# OksLab_CanToUsb_HW01.net
KiCad netlist of a schematic drawn in Altium Designer
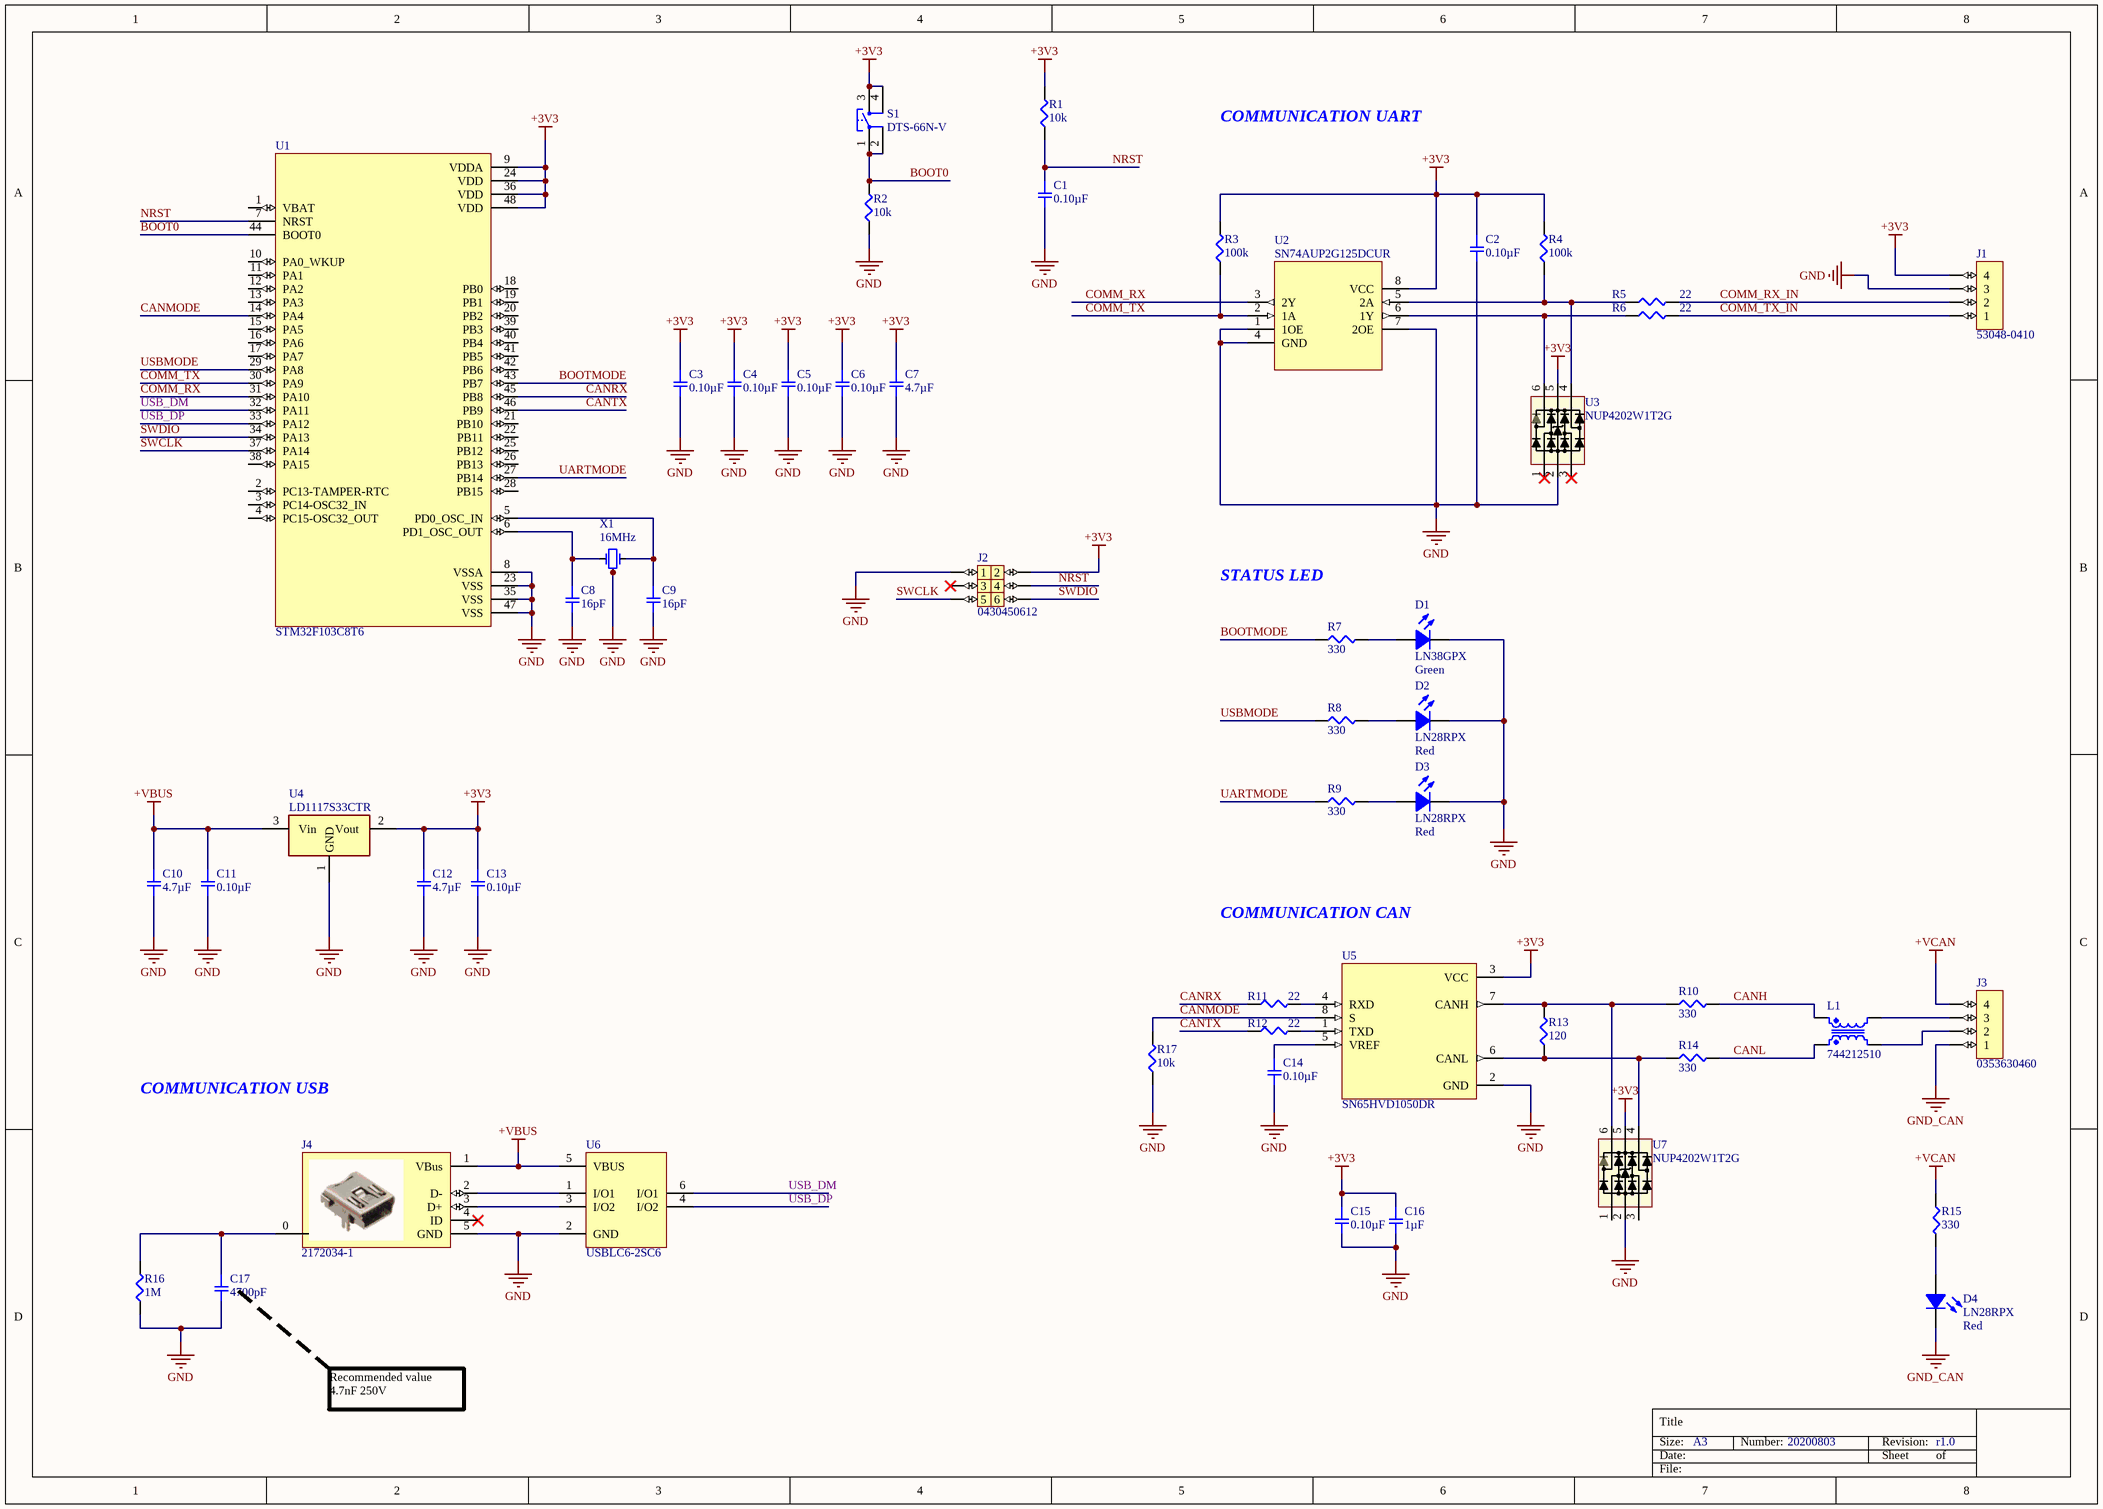
[diagram p0: OksLab_CanToUsb_HW01.SchDoc]

(export (version "E")
  (design (tool "Eeschema 10.0.6"))
  (components
    (comp (ref "C1")
      (value "0.10µF")
      (footprint "SMD-0603C")
      (description "CAP CER 0.1UF 50V X7R 0603")
      (fields
        (field (name "DIGI-KEY PART NUMBER") "490-5798-1-ND")
        (field (name "PART NUMBER") "GCJ188R71H104KA12D")
      )
      (libsource (lib "capacitor_murata_0603") (part "GCJ188R71H104KA12D"))
    )
    (comp (ref "C2")
      (value "0.10µF")
      (footprint "SMD-0603C")
      (description "CAP CER 0.1UF 50V X7R 0603")
      (fields
        (field (name "DIGI-KEY PART NUMBER") "490-5798-1-ND")
        (field (name "MANUFACTURER") "Murata Electronics North America")
      )
      (libsource (lib "capacitor_murata_0603") (part "GCJ188R71H104KA12D"))
    )
    (comp (ref "C3")
      (value "0.10µF")
      (footprint "SMD-0603C")
      (description "CAP CER 0.1UF 50V X7R 0603")
      (fields
        (field (name "DIGI-KEY PART NUMBER") "490-5798-1-ND")
        (field (name "PART NUMBER") "GCJ188R71H104KA12D")
      )
      (libsource (lib "capacitor_murata_0603") (part "GCJ188R71H104KA12D"))
    )
    (comp (ref "C4")
      (value "0.10µF")
      (footprint "SMD-0603C")
      (description "CAP CER 0.1UF 50V X7R 0603")
      (fields
        (field (name "DIGI-KEY PART NUMBER") "490-5798-1-ND")
        (field (name "PART NUMBER") "GCJ188R71H104KA12D")
      )
      (libsource (lib "capacitor_murata_0603") (part "GCJ188R71H104KA12D"))
    )
    (comp (ref "C5")
      (value "0.10µF")
      (footprint "SMD-0603C")
      (description "CAP CER 0.1UF 50V X7R 0603")
      (fields
        (field (name "DIGI-KEY PART NUMBER") "490-5798-1-ND")
        (field (name "PART NUMBER") "GCJ188R71H104KA12D")
      )
      (libsource (lib "capacitor_murata_0603") (part "GCJ188R71H104KA12D"))
    )
    (comp (ref "C6")
      (value "0.10µF")
      (footprint "SMD-0603C")
      (description "CAP CER 0.1UF 50V X7R 0603")
      (fields
        (field (name "DIGI-KEY PART NUMBER") "490-5798-1-ND")
        (field (name "PART NUMBER") "GCJ188R71H104KA12D")
      )
      (libsource (lib "capacitor_murata_0603") (part "GCJ188R71H104KA12D"))
    )
    (comp (ref "C7")
      (value "4.7µF")
      (footprint "SMD-0603C")
      (description "CAP CER 4.7UF 16V X5R 0603")
      (fields
        (field (name "DIGI-KEY PART NUMBER") "490-10481-1-ND")
        (field (name "PART NUMBER") "GRM188R61C475KAAJD")
      )
      (libsource (lib "capacitor_murata_0603") (part "GRM188R61C475KAAJD"))
    )
    (comp (ref "C8")
      (value "16pF")
      (footprint "SMD-0603C")
      (description "CAP CER 16PF 50V NP0 0603")
      (fields
        (field (name "DIGI-KEY PART NUMBER") "490-8003-1-ND")
        (field (name "PART NUMBER") "GCM1885C1H160JA16D")
      )
      (libsource (lib "capacitor_murata_0603") (part "GCM1885C1H160JA16D"))
    )
    (comp (ref "C9")
      (value "16pF")
      (footprint "SMD-0603C")
      (description "CAP CER 16PF 50V NP0 0603")
      (fields
        (field (name "DIGI-KEY PART NUMBER") "490-8003-1-ND")
        (field (name "PART NUMBER") "GCM1885C1H160JA16D")
      )
      (libsource (lib "capacitor_murata_0603") (part "GCM1885C1H160JA16D"))
    )
    (comp (ref "C10")
      (value "4.7µF")
      (footprint "SMD-0603C")
      (description "CAP CER 4.7UF 16V X5R 0603")
      (fields
        (field (name "DIGI-KEY PART NUMBER") "490-10481-1-ND")
        (field (name "PART NUMBER") "GRM188R61C475KAAJD")
      )
      (libsource (lib "capacitor_murata_0603") (part "GRM188R61C475KAAJD"))
    )
    (comp (ref "C11")
      (value "0.10µF")
      (footprint "SMD-0603C")
      (description "CAP CER 0.1UF 50V X7R 0603")
      (fields
        (field (name "DIGI-KEY PART NUMBER") "490-5798-1-ND")
        (field (name "PART NUMBER") "GCJ188R71H104KA12D")
      )
      (libsource (lib "capacitor_murata_0603") (part "GCJ188R71H104KA12D"))
    )
    (comp (ref "C12")
      (value "4.7µF")
      (footprint "SMD-0603C")
      (description "CAP CER 4.7UF 16V X5R 0603")
      (fields
        (field (name "DIGI-KEY PART NUMBER") "490-10481-1-ND")
        (field (name "PART NUMBER") "GRM188R61C475KAAJD")
      )
      (libsource (lib "capacitor_murata_0603") (part "GRM188R61C475KAAJD"))
    )
    (comp (ref "C13")
      (value "0.10µF")
      (footprint "SMD-0603C")
      (description "CAP CER 0.1UF 50V X7R 0603")
      (fields
        (field (name "DIGI-KEY PART NUMBER") "490-5798-1-ND")
        (field (name "PART NUMBER") "GCJ188R71H104KA12D")
      )
      (libsource (lib "capacitor_murata_0603") (part "GCJ188R71H104KA12D"))
    )
    (comp (ref "C14")
      (value "0.10µF")
      (footprint "SMD-0603C")
      (description "CAP CER 0.1UF 50V X7R 0603")
      (fields
        (field (name "DIGI-KEY PART NUMBER") "490-5798-1-ND")
        (field (name "PART NUMBER") "GCJ188R71H104KA12D")
      )
      (libsource (lib "capacitor_murata_0603") (part "GCJ188R71H104KA12D"))
    )
    (comp (ref "C15")
      (value "0.10µF")
      (footprint "SMD-0603C")
      (description "CAP CER 0.1UF 50V X7R 0603")
      (fields
        (field (name "DIGI-KEY PART NUMBER") "490-5798-1-ND")
        (field (name "PART NUMBER") "GCJ188R71H104KA12D")
      )
      (libsource (lib "capacitor_murata_0603") (part "GCJ188R71H104KA12D"))
    )
    (comp (ref "C16")
      (value "1µF")
      (footprint "SMD-0603C")
      (description "CAP CER 1UF 16V X7R 0603")
      (fields
        (field (name "DIGI-KEY PART NUMBER") "490-5241-1-ND")
        (field (name "PART NUMBER") "GCM188R71C105KA64D")
      )
      (libsource (lib "capacitor_murata_0603") (part "GCM188R71C105KA64D"))
    )
    (comp (ref "C17")
      (value "4700pF")
      (footprint "SMD-0805C")
      (description "CAP CER 4700PF 250V X7R 0805")
      (fields
        (field (name "DIGI-KEY PART NUMBER") "490-3532-1-ND")
        (field (name "MANUFACTURER") "Murata Electronics North America")
      )
      (libsource (lib "capacitor_murata_0805") (part "GRM21AR72E472KW01D"))
    )
    (comp (ref "D1")
      (value "LN38GPX")
      (footprint "Led-3mm-Green-h7")
      (description "LED GREEN 3MM ROUND T/H")
      (fields
        (field (name "MANUFACTURER") "Panasonic Electronic Components")
        (field (name "BASE PART NUMBER") "LN*8")
        (field (name "COLOR") "Green")
      )
      (libsource (lib "Altium_Lib") (part "LED_GREEN__LN38GPX"))
    )
    (comp (ref "D2")
      (value "LN28RPX")
      (footprint "Led-3mm-Red-h7")
      (description "LED RED DIFF 3MM ROUND T/H")
      (fields
        (field (name "MANUFACTURER") "Panasonic Electronic Components")
        (field (name "LENS COLOR") "Red")
      )
      (libsource (lib "Altium_Lib") (part "LED_RED__LN28RPX"))
    )
    (comp (ref "D3")
      (value "LN28RPX")
      (footprint "Led-3mm-Red-h7")
      (description "LED RED DIFF 3MM ROUND T/H")
      (fields
        (field (name "MANUFACTURER") "Panasonic Electronic Components")
        (field (name "LENS COLOR") "Red")
      )
      (libsource (lib "Altium_Lib") (part "LED_RED__LN28RPX"))
    )
    (comp (ref "D4")
      (value "LN28RPX")
      (footprint "Led-3mm-Red-h7")
      (description "LED RED DIFF 3MM ROUND T/H")
      (fields
        (field (name "MANUFACTURER") "Panasonic Electronic Components")
        (field (name "LENS COLOR") "Red")
      )
      (libsource (lib "Altium_Lib") (part "LED_RED__LN28RPX"))
    )
    (comp (ref "J1")
      (value "53048-0410")
      (footprint "CONN_4_POS__0530480410")
      (description "CONN HEADER R/A 4POS 1.25MM")
      (fields (field (name "MANUFACTURER") "Molex"))
      (libsource (lib "Altium_Lib") (part "CONN_4_POS__0530480410"))
    )
    (comp (ref "J2")
      (value "0430450612")
      (footprint "CONN_6_POS__0430450612")
      (description "CONN HEADER 6POS 3MM VERT TIN")
      (fields (field (name "MANUFACTURER") "Molex, LLC"))
      (libsource (lib "Altium_Lib") (part "CONN_6_POS__0430450612"))
    )
    (comp (ref "J3")
      (value "0353630460")
      (footprint "CONN_4_POS__0353630460")
      (description "CONN HEADER 4POS 2MM R/A TIN")
      (fields (field (name "MANUFACTURER") "Molex Connector Corporation"))
      (libsource (lib "Altium_Lib") (part "CONN_4_POS__0353630460"))
    )
    (comp (ref "J4")
      (value "2172034-1")
      (footprint "USB_MINI__2172034-1")
      (description "CONN RCPT USB2.0 MINI B 5P R/A")
      (fields (field (name "MANUFACTURER") "TE Connectivity AMP"))
      (libsource (lib "Altium_Lib") (part "USB_MINI__2172034-1"))
    )
    (comp (ref "L1")
      (value "744212510")
      (footprint "CM_6.50mm x 3.60mm")
      (description "Common Mode Filters / Chokes WE-SL1 SMD Ln Filter 2x51uH 300ohm")
      (fields (field (name "MANUFACTURER") "Wurth Electronics") (field (name "TOLERANCE") "50%"))
      (libsource (lib "Altium_Lib") (part "CM__744212510"))
    )
    (comp (ref "R1")
      (value "10k")
      (footprint "SMD-0603-RES")
      (description "RES SMD 10K OHM 1% 1/10W 0603")
      (fields
        (field (name "PART NUMBER") "ERJ-3EKF1002V")
        (field (name "DIGI-KEY PART NUMBER") "P10.0KHCT-ND")
      )
      (libsource (lib "Panasonic_ERJ_0603") (part "ERJ-3EKF1002V"))
    )
    (comp (ref "R2")
      (value "10k")
      (footprint "SMD-0603-RES")
      (description "RES SMD 10K OHM 1% 1/10W 0603")
      (fields
        (field (name "PART NUMBER") "ERJ-3EKF1002V")
        (field (name "DIGI-KEY PART NUMBER") "P10.0KHCT-ND")
      )
      (libsource (lib "Panasonic_ERJ_0603") (part "ERJ-3EKF1002V"))
    )
    (comp (ref "R3")
      (value "100k")
      (footprint "SMD-0603-RES")
      (description "RES SMD 100K OHM 1% 1/10W 0603")
      (fields
        (field (name "PART NUMBER") "ERJ-3EKF1003V")
        (field (name "DIGI-KEY PART NUMBER") "P100KHCT-ND")
      )
      (libsource (lib "Panasonic_ERJ_0603") (part "ERJ-3EKF1003V"))
    )
    (comp (ref "R4")
      (value "100k")
      (footprint "SMD-0603-RES")
      (description "RES SMD 100K OHM 1% 1/10W 0603")
      (fields
        (field (name "PART NUMBER") "ERJ-3EKF1003V")
        (field (name "DIGI-KEY PART NUMBER") "P100KHCT-ND")
      )
      (libsource (lib "Panasonic_ERJ_0603") (part "ERJ-3EKF1003V"))
    )
    (comp (ref "R5")
      (value "22")
      (footprint "SMD-0603-RES")
      (description "RES SMD 22 OHM 1% 1/10W 0603")
      (fields
        (field (name "PART NUMBER") "ERJ-3EKF22R0V")
        (field (name "DIGI-KEY PART NUMBER") "P22.0HCT-ND")
      )
      (libsource (lib "Panasonic_ERJ_0603") (part "ERJ-3EKF22R0V"))
    )
    (comp (ref "R6")
      (value "22")
      (footprint "SMD-0603-RES")
      (description "RES SMD 22 OHM 1% 1/10W 0603")
      (fields
        (field (name "PART NUMBER") "ERJ-3EKF22R0V")
        (field (name "DIGI-KEY PART NUMBER") "P22.0HCT-ND")
      )
      (libsource (lib "Panasonic_ERJ_0603") (part "ERJ-3EKF22R0V"))
    )
    (comp (ref "R7")
      (value "330")
      (footprint "SMD-0603-RES")
      (description "RES SMD 330 OHM 1% 1/10W 0603")
      (fields (field (name "PART NUMBER") "ERJ-3EKF3300V") (field (name "DIGI-KEY PART NUMBER") "P330HCT-ND"))
      (libsource (lib "Panasonic_ERJ_0603") (part "ERJ-3EKF3300V"))
    )
    (comp (ref "R8")
      (value "330")
      (footprint "SMD-0603-RES")
      (description "RES SMD 330 OHM 1% 1/10W 0603")
      (fields (field (name "PART NUMBER") "ERJ-3EKF3300V") (field (name "DIGI-KEY PART NUMBER") "P330HCT-ND"))
      (libsource (lib "Panasonic_ERJ_0603") (part "ERJ-3EKF3300V"))
    )
    (comp (ref "R9")
      (value "330")
      (footprint "SMD-0603-RES")
      (description "RES SMD 330 OHM 1% 1/10W 0603")
      (fields (field (name "PART NUMBER") "ERJ-3EKF3300V") (field (name "DIGI-KEY PART NUMBER") "P330HCT-ND"))
      (libsource (lib "Panasonic_ERJ_0603") (part "ERJ-3EKF3300V"))
    )
    (comp (ref "R10")
      (value "330")
      (footprint "SMD-0603-RES")
      (description "RES SMD 330 OHM 1% 1/10W 0603")
      (fields (field (name "PART NUMBER") "ERJ-3EKF3300V") (field (name "DIGI-KEY PART NUMBER") "P330HCT-ND"))
      (libsource (lib "Panasonic_ERJ_0603") (part "ERJ-3EKF3300V"))
    )
    (comp (ref "R11")
      (value "22")
      (footprint "SMD-0603-RES")
      (description "RES SMD 22 OHM 1% 1/10W 0603")
      (fields
        (field (name "PART NUMBER") "ERJ-3EKF22R0V")
        (field (name "DIGI-KEY PART NUMBER") "P22.0HCT-ND")
      )
      (libsource (lib "Panasonic_ERJ_0603") (part "ERJ-3EKF22R0V"))
    )
    (comp (ref "R12")
      (value "22")
      (footprint "SMD-0603-RES")
      (description "RES SMD 22 OHM 1% 1/10W 0603")
      (fields
        (field (name "PART NUMBER") "ERJ-3EKF22R0V")
        (field (name "DIGI-KEY PART NUMBER") "P22.0HCT-ND")
      )
      (libsource (lib "Panasonic_ERJ_0603") (part "ERJ-3EKF22R0V"))
    )
    (comp (ref "R13")
      (value "120")
      (footprint "SMD-0603-RES")
      (description "RES SMD 120 OHM 1% 1/10W 0603")
      (fields (field (name "PART NUMBER") "ERJ-3EKF1200V") (field (name "DIGI-KEY PART NUMBER") "P120HCT-ND"))
      (libsource (lib "Panasonic_ERJ_0603") (part "ERJ-3EKF1200V"))
    )
    (comp (ref "R14")
      (value "330")
      (footprint "SMD-0603-RES")
      (description "RES SMD 330 OHM 1% 1/10W 0603")
      (fields (field (name "PART NUMBER") "ERJ-3EKF3300V") (field (name "DIGI-KEY PART NUMBER") "P330HCT-ND"))
      (libsource (lib "Panasonic_ERJ_0603") (part "ERJ-3EKF3300V"))
    )
    (comp (ref "R15")
      (value "330")
      (footprint "SMD-0603-RES")
      (description "RES SMD 330 OHM 1% 1/10W 0603")
      (fields (field (name "PART NUMBER") "ERJ-3EKF3300V") (field (name "DIGI-KEY PART NUMBER") "P330HCT-ND"))
      (libsource (lib "Panasonic_ERJ_0603") (part "ERJ-3EKF3300V"))
    )
    (comp (ref "R16")
      (value "1M")
      (footprint "SMD-0603-RES")
      (description "RES SMD 1M OHM 1% 1/10W 0603")
      (fields
        (field (name "DIGI-KEY PART NUMBER") "P1.00MHCT-ND")
        (field (name "MANUFACTURER") "Panasonic Electronic Components")
      )
      (libsource (lib "Panasonic_ERJ_0603") (part "ERJ-3EKF1004V"))
    )
    (comp (ref "R17")
      (value "10k")
      (footprint "SMD-0603-RES")
      (description "RES SMD 10K OHM 1% 1/10W 0603")
      (fields
        (field (name "PART NUMBER") "ERJ-3EKF1002V")
        (field (name "DIGI-KEY PART NUMBER") "P10.0KHCT-ND")
      )
      (libsource (lib "Panasonic_ERJ_0603") (part "ERJ-3EKF1002V"))
    )
    (comp (ref "S1")
      (value "DTS-66N-V")
      (footprint "Tact_THD_6x6_13mm")
      (description "Tactile Switches 6x6mm 13mm 160gf BROWN")
      (fields (field (name "MANUFACTURER") "Diptronics"))
      (libsource (lib "Altium_Lib") (part "SWITCH_TACTILE__DTS-66N-V"))
    )
    (comp (ref "U1")
      (value "STM32F103C8T6")
      (footprint "QFN48-(7mmX7mm)")
      (description "IC MCU 32-Bit 72MHz 64kB FLASH LQFP48")
      (fields (field (name "MF") "STMicroelectronics"))
      (libsource (lib "Altium_Lib") (part "STM32F103C8T6"))
    )
    (comp (ref "U2")
      (value "SN74AUP2G125DCUR")
      (footprint "VFSOP_8")
      (description "Low-Power Dual Bus Buffer Gate With 3-State Outputs 8-VSSOP -40 to 85")
      (fields (field (name "MANUFACTURER") "Texas Instruments"))
      (libsource (lib "Altium_Lib") (part "SN74AUP2G125DCUR"))
    )
    (comp (ref "U3")
      (value "NUP4202W1T2G")
      (footprint "SOT-363")
      (description "TVS DIODE 5VWM 14.5VC SOT363")
      (fields (field (name "MANUFACTURER") "ON Semiconductor"))
      (libsource (lib "Altium_Lib") (part "NUP4202W1T2G"))
    )
    (comp (ref "U4")
      (value "LD1117S33CTR")
      (footprint "SOT223-3N")
      (description "STMICROELECTRONICS - LD1117S33CTR - IC, V REG, LDO 3.3V, SMD")
      (fields (field (name "MANUFACTURER") "STMICROELECTRONICS"))
      (libsource (lib "Altium_Lib") (part "LD1117S33TR"))
    )
    (comp (ref "U5")
      (value "SN65HVD1050DR")
      (footprint "SOIC-8_L")
      (description "High-Speed CAN Transceiver with Silent Mode 8-SOIC -40 to 125")
      (fields (field (name "DIGI-KEY_PART_NUMBER") "296-26335-1-ND") (field (name "MF") "Texas Instruments"))
      (libsource (lib "Altium_Lib") (part "SN65HVD1050DR"))
    )
    (comp (ref "U6")
      (value "USBLC6-2SC6")
      (footprint "SOT23-6")
      (description "TVS DIODE 5.25V 17V SOT23-6")
      (fields (field (name "MANUFACTURER") "STMicroelectronics") (field (name "BASE PART NUMBER") "USBLC6-2"))
      (libsource (lib "KRNK_Altium") (part "USBLC6-2SC6"))
    )
    (comp (ref "U7")
      (value "NUP4202W1T2G")
      (footprint "SOT-363")
      (description "TVS DIODE 5VWM 14.5VC SOT363")
      (fields (field (name "MANUFACTURER") "ON Semiconductor"))
      (libsource (lib "Altium_Lib") (part "NUP4202W1T2G"))
    )
    (comp (ref "X1")
      (value "7M-16.000MAAJ-T")
      (footprint "XTAL_3.2mm_2.5mm_4pad")
      (description "Crystal 16MHz ±30ppm (Tol) ±30ppm (Stability) 18pF FUND 100Ohm 4-Pin SMD T/R")
      (fields
        (field (name "MANUFACTURER") "TXC")
        (field (name "FREQUENCY") "16MHz")
        (field (name "TOLERANCE") "30ppm")
      )
      (libsource (lib "Altium_Lib") (part "CRYSTAL__7M-16.000MAAJ-T"))
    )
  )
  (nets
    (net (code "1") (name "+3V3") (class "Default")
      (node (ref "C12") (pin "1") (pinfunction "1_1") (pintype "passive"))
      (node (ref "C13") (pin "1") (pinfunction "1_1") (pintype "passive"))
      (node (ref "C15") (pin "1") (pinfunction "1_1") (pintype "passive"))
      (node (ref "C16") (pin "1") (pinfunction "1_1") (pintype "passive"))
      (node (ref "C2") (pin "1") (pinfunction "1_1") (pintype "passive"))
      (node (ref "C3") (pin "1") (pinfunction "1_1") (pintype "passive"))
      (node (ref "C4") (pin "1") (pinfunction "1_1") (pintype "passive"))
      (node (ref "C5") (pin "1") (pinfunction "1_1") (pintype "passive"))
      (node (ref "C6") (pin "1") (pinfunction "1_1") (pintype "passive"))
      (node (ref "C7") (pin "1") (pinfunction "1_1") (pintype "passive"))
      (node (ref "J1") (pin "4") (pinfunction "4_4") (pintype "bidirectional"))
      (node (ref "J2") (pin "2") (pinfunction "2_2") (pintype "bidirectional"))
      (node (ref "R1") (pin "2") (pinfunction "2_2") (pintype "passive"))
      (node (ref "R3") (pin "2") (pinfunction "2_2") (pintype "passive"))
      (node (ref "R4") (pin "2") (pinfunction "2_2") (pintype "passive"))
      (node (ref "S1") (pin "3") (pinfunction "3_3") (pintype "passive"))
      (node (ref "S1") (pin "4") (pinfunction "4_4") (pintype "passive"))
      (node (ref "U1") (pin "24") (pinfunction "VDD_24") (pintype "passive"))
      (node (ref "U1") (pin "36") (pinfunction "VDD_36") (pintype "passive"))
      (node (ref "U1") (pin "48") (pinfunction "VDD_48") (pintype "passive"))
      (node (ref "U1") (pin "9") (pinfunction "VDDA_9") (pintype "passive"))
      (node (ref "U2") (pin "8") (pinfunction "VCC_8") (pintype "passive"))
      (node (ref "U3") (pin "5") (pinfunction "5_5") (pintype "passive"))
      (node (ref "U4") (pin "2") (pinfunction "Vout_2") (pintype "passive"))
      (node (ref "U5") (pin "3") (pinfunction "VCC_3") (pintype "power_in"))
      (node (ref "U7") (pin "5") (pinfunction "5_5") (pintype "passive"))
    )
    (net (code "2") (name "+VBUS") (class "Default")
      (node (ref "C10") (pin "1") (pinfunction "1_1") (pintype "passive"))
      (node (ref "C11") (pin "1") (pinfunction "1_1") (pintype "passive"))
      (node (ref "J4") (pin "1") (pinfunction "VBus_1") (pintype "power_in"))
      (node (ref "U4") (pin "3") (pinfunction "Vin_3") (pintype "passive"))
      (node (ref "U6") (pin "5") (pinfunction "VBUS_5") (pintype "passive"))
    )
    (net (code "3") (name "+VCAN") (class "Default")
      (node (ref "J3") (pin "4") (pinfunction "4_4") (pintype "bidirectional"))
      (node (ref "R15") (pin "1") (pinfunction "1_1") (pintype "passive"))
    )
    (net (code "4") (name "/BOOT0") (class "Default")
      (node (ref "R2") (pin "2") (pinfunction "2_2") (pintype "passive"))
      (node (ref "S1") (pin "1") (pinfunction "1_1") (pintype "passive"))
      (node (ref "S1") (pin "2") (pinfunction "2_2") (pintype "passive"))
      (node (ref "U1") (pin "44") (pinfunction "BOOT0_44") (pintype "passive"))
    )
    (net (code "5") (name "/BOOTMODE") (class "Default")
      (node (ref "R7") (pin "1") (pinfunction "1_1") (pintype "passive"))
      (node (ref "U1") (pin "43") (pinfunction "PB7_43") (pintype "bidirectional"))
    )
    (net (code "6") (name "/CANH") (class "Default")
      (node (ref "L1") (pin "3") (pinfunction "3_3") (pintype "passive"))
      (node (ref "R10") (pin "2") (pinfunction "2_2") (pintype "passive"))
    )
    (net (code "7") (name "/CANL") (class "Default")
      (node (ref "L1") (pin "1") (pinfunction "1_1") (pintype "passive"))
      (node (ref "R14") (pin "2") (pinfunction "2_2") (pintype "passive"))
    )
    (net (code "8") (name "/CANMODE") (class "Default")
      (node (ref "R17") (pin "2") (pinfunction "2_2") (pintype "passive"))
      (node (ref "U1") (pin "14") (pinfunction "PA4_14") (pintype "bidirectional"))
      (node (ref "U5") (pin "8") (pinfunction "S_8") (pintype "input"))
    )
    (net (code "9") (name "/CANRX") (class "Default")
      (node (ref "R11") (pin "1") (pinfunction "1_1") (pintype "passive"))
      (node (ref "U1") (pin "45") (pinfunction "PB8_45") (pintype "bidirectional"))
    )
    (net (code "10") (name "/CANTX") (class "Default")
      (node (ref "R12") (pin "1") (pinfunction "1_1") (pintype "passive"))
      (node (ref "U1") (pin "46") (pinfunction "PB9_46") (pintype "bidirectional"))
    )
    (net (code "11") (name "/COMM_RX") (class "Default")
      (node (ref "U1") (pin "31") (pinfunction "PA10_31") (pintype "bidirectional"))
      (node (ref "U2") (pin "3") (pinfunction "2Y_3") (pintype "output"))
    )
    (net (code "12") (name "/COMM_RX_IN") (class "Default")
      (node (ref "J1") (pin "2") (pinfunction "2_2") (pintype "bidirectional"))
      (node (ref "R5") (pin "2") (pinfunction "2_2") (pintype "passive"))
    )
    (net (code "13") (name "/COMM_TX") (class "Default")
      (node (ref "R3") (pin "1") (pinfunction "1_1") (pintype "passive"))
      (node (ref "U1") (pin "30") (pinfunction "PA9_30") (pintype "bidirectional"))
      (node (ref "U2") (pin "2") (pinfunction "1A_2") (pintype "input"))
    )
    (net (code "14") (name "/COMM_TX_IN") (class "Default")
      (node (ref "J1") (pin "1") (pinfunction "1_1") (pintype "bidirectional"))
      (node (ref "R6") (pin "2") (pinfunction "2_2") (pintype "passive"))
    )
    (net (code "15") (name "/NRST") (class "Default")
      (node (ref "C1") (pin "1") (pinfunction "1_1") (pintype "passive"))
      (node (ref "J2") (pin "4") (pinfunction "4_4") (pintype "bidirectional"))
      (node (ref "R1") (pin "1") (pinfunction "1_1") (pintype "passive"))
      (node (ref "U1") (pin "7") (pinfunction "NRST_7") (pintype "passive"))
    )
    (net (code "16") (name "/SWCLK") (class "Default")
      (node (ref "J2") (pin "5") (pinfunction "5_5") (pintype "bidirectional"))
      (node (ref "U1") (pin "37") (pinfunction "PA14_37") (pintype "bidirectional"))
    )
    (net (code "17") (name "/SWDIO") (class "Default")
      (node (ref "J2") (pin "6") (pinfunction "6_6") (pintype "bidirectional"))
      (node (ref "U1") (pin "34") (pinfunction "PA13_34") (pintype "bidirectional"))
    )
    (net (code "18") (name "/UARTMODE") (class "Default")
      (node (ref "R9") (pin "1") (pinfunction "1_1") (pintype "passive"))
      (node (ref "U1") (pin "27") (pinfunction "PB14_27") (pintype "bidirectional"))
    )
    (net (code "19") (name "/USBMODE") (class "Default")
      (node (ref "R8") (pin "1") (pinfunction "1_1") (pintype "passive"))
      (node (ref "U1") (pin "29") (pinfunction "PA8_29") (pintype "bidirectional"))
    )
    (net (code "20") (name "/USB_DM") (class "Default")
      (node (ref "U1") (pin "32") (pinfunction "PA11_32") (pintype "bidirectional"))
      (node (ref "U6") (pin "6") (pinfunction "I/O1_6") (pintype "passive"))
    )
    (net (code "21") (name "/USB_DP") (class "Default")
      (node (ref "U1") (pin "33") (pinfunction "PA12_33") (pintype "bidirectional"))
      (node (ref "U6") (pin "4") (pinfunction "I/O2_4") (pintype "passive"))
    )
    (net (code "22") (name "GND") (class "Default")
      (node (ref "C1") (pin "2") (pinfunction "2_2") (pintype "passive"))
      (node (ref "C10") (pin "2") (pinfunction "2_2") (pintype "passive"))
      (node (ref "C11") (pin "2") (pinfunction "2_2") (pintype "passive"))
      (node (ref "C12") (pin "2") (pinfunction "2_2") (pintype "passive"))
      (node (ref "C13") (pin "2") (pinfunction "2_2") (pintype "passive"))
      (node (ref "C14") (pin "2") (pinfunction "2_2") (pintype "passive"))
      (node (ref "C15") (pin "2") (pinfunction "2_2") (pintype "passive"))
      (node (ref "C16") (pin "2") (pinfunction "2_2") (pintype "passive"))
      (node (ref "C17") (pin "2") (pinfunction "2_2") (pintype "passive"))
      (node (ref "C2") (pin "2") (pinfunction "2_2") (pintype "passive"))
      (node (ref "C3") (pin "2") (pinfunction "2_2") (pintype "passive"))
      (node (ref "C4") (pin "2") (pinfunction "2_2") (pintype "passive"))
      (node (ref "C5") (pin "2") (pinfunction "2_2") (pintype "passive"))
      (node (ref "C6") (pin "2") (pinfunction "2_2") (pintype "passive"))
      (node (ref "C7") (pin "2") (pinfunction "2_2") (pintype "passive"))
      (node (ref "C8") (pin "2") (pinfunction "2_2") (pintype "passive"))
      (node (ref "C9") (pin "2") (pinfunction "2_2") (pintype "passive"))
      (node (ref "D1") (pin "2") (pinfunction "K_2") (pintype "passive"))
      (node (ref "D2") (pin "2") (pinfunction "K_2") (pintype "passive"))
      (node (ref "D3") (pin "2") (pinfunction "K_2") (pintype "passive"))
      (node (ref "J1") (pin "3") (pinfunction "3_3") (pintype "bidirectional"))
      (node (ref "J2") (pin "1") (pinfunction "1_1") (pintype "bidirectional"))
      (node (ref "J4") (pin "5") (pinfunction "GND_5") (pintype "power_in"))
      (node (ref "R16") (pin "1") (pinfunction "1_1") (pintype "passive"))
      (node (ref "R17") (pin "1") (pinfunction "1_1") (pintype "passive"))
      (node (ref "R2") (pin "1") (pinfunction "1_1") (pintype "passive"))
      (node (ref "U1") (pin "23") (pinfunction "VSS_23") (pintype "passive"))
      (node (ref "U1") (pin "35") (pinfunction "VSS_35") (pintype "passive"))
      (node (ref "U1") (pin "47") (pinfunction "VSS_47") (pintype "passive"))
      (node (ref "U1") (pin "8") (pinfunction "VSSA_8") (pintype "passive"))
      (node (ref "U2") (pin "1") (pinfunction "1OE_1") (pintype "passive"))
      (node (ref "U2") (pin "4") (pinfunction "GND_4") (pintype "passive"))
      (node (ref "U2") (pin "7") (pinfunction "2OE_7") (pintype "passive"))
      (node (ref "U3") (pin "2") (pinfunction "2_2") (pintype "passive"))
      (node (ref "U4") (pin "1") (pinfunction "GND_1") (pintype "passive"))
      (node (ref "U5") (pin "2") (pinfunction "GND_2") (pintype "power_in"))
      (node (ref "U6") (pin "2") (pinfunction "GND_2") (pintype "passive"))
      (node (ref "U7") (pin "2") (pinfunction "2_2") (pintype "passive"))
      (node (ref "X1") (pin "2") (pinfunction "GND_2") (pintype "power_in"))
      (node (ref "X1") (pin "4") (pinfunction "GND_4") (pintype "power_in"))
    )
    (net (code "23") (name "GND_CAN") (class "Default")
      (node (ref "D4") (pin "2") (pinfunction "K_2") (pintype "passive"))
      (node (ref "J3") (pin "1") (pinfunction "1_1") (pintype "bidirectional"))
    )
    (net (code "24") (name "Net-(D1-A)") (class "Default")
      (node (ref "D1") (pin "1") (pinfunction "A_1") (pintype "passive"))
      (node (ref "R7") (pin "2") (pinfunction "2_2") (pintype "passive"))
    )
    (net (code "25") (name "Net-(D2-A)") (class "Default")
      (node (ref "D2") (pin "1") (pinfunction "A_1") (pintype "passive"))
      (node (ref "R8") (pin "2") (pinfunction "2_2") (pintype "passive"))
    )
    (net (code "26") (name "Net-(D3-A)") (class "Default")
      (node (ref "D3") (pin "1") (pinfunction "A_1") (pintype "passive"))
      (node (ref "R9") (pin "2") (pinfunction "2_2") (pintype "passive"))
    )
    (net (code "27") (name "Net-(D4-A)") (class "Default")
      (node (ref "D4") (pin "1") (pinfunction "A_1") (pintype "passive"))
      (node (ref "R15") (pin "2") (pinfunction "2_2") (pintype "passive"))
    )
    (net (code "28") (name "Net-(J3-Pad2)") (class "Default")
      (node (ref "J3") (pin "2") (pinfunction "2_2") (pintype "bidirectional"))
      (node (ref "L1") (pin "5") (pinfunction "5_5") (pintype "passive"))
    )
    (net (code "29") (name "Net-(J3-Pad3)") (class "Default")
      (node (ref "J3") (pin "3") (pinfunction "3_3") (pintype "bidirectional"))
      (node (ref "L1") (pin "4") (pinfunction "4_4") (pintype "passive"))
    )
    (net (code "30") (name "Net-(J4-D+)") (class "Default")
      (node (ref "J4") (pin "3") (pinfunction "D+_3") (pintype "bidirectional"))
      (node (ref "U6") (pin "3") (pinfunction "I/O2_3") (pintype "passive"))
    )
    (net (code "31") (name "Net-(J4-D-)") (class "Default")
      (node (ref "J4") (pin "2") (pinfunction "D-_2") (pintype "bidirectional"))
      (node (ref "U6") (pin "1") (pinfunction "I/O1_1") (pintype "passive"))
    )
    (net (code "32") (name "Net-(J4-Shield)") (class "Default")
      (node (ref "C17") (pin "1") (pinfunction "1_1") (pintype "passive"))
      (node (ref "J4") (pin "0") (pinfunction "Shield_0") (pintype "passive"))
      (node (ref "R16") (pin "2") (pinfunction "2_2") (pintype "passive"))
    )
    (net (code "33") (name "Net-(U1-PD0_OSC_IN)") (class "Default")
      (node (ref "C9") (pin "1") (pinfunction "1_1") (pintype "passive"))
      (node (ref "U1") (pin "5") (pinfunction "PD0_OSC_IN_5") (pintype "bidirectional"))
      (node (ref "X1") (pin "3") (pinfunction "OSC2_3") (pintype "passive"))
    )
    (net (code "34") (name "Net-(U1-PD1_OSC_OUT)") (class "Default")
      (node (ref "C8") (pin "1") (pinfunction "1_1") (pintype "passive"))
      (node (ref "U1") (pin "6") (pinfunction "PD1_OSC_OUT_6") (pintype "bidirectional"))
      (node (ref "X1") (pin "1") (pinfunction "OSC1_1") (pintype "passive"))
    )
    (net (code "35") (name "Net-(U2-1Y)") (class "Default")
      (node (ref "R6") (pin "1") (pinfunction "1_1") (pintype "passive"))
      (node (ref "U2") (pin "6") (pinfunction "1Y_6") (pintype "output"))
      (node (ref "U3") (pin "6") (pinfunction "6_6") (pintype "passive"))
    )
    (net (code "36") (name "Net-(U2-2A)") (class "Default")
      (node (ref "R4") (pin "1") (pinfunction "1_1") (pintype "passive"))
      (node (ref "R5") (pin "1") (pinfunction "1_1") (pintype "passive"))
      (node (ref "U2") (pin "5") (pinfunction "2A_5") (pintype "input"))
      (node (ref "U3") (pin "4") (pinfunction "4_4") (pintype "passive"))
    )
    (net (code "37") (name "Net-(U5-CANH)") (class "Default")
      (node (ref "R10") (pin "1") (pinfunction "1_1") (pintype "passive"))
      (node (ref "R13") (pin "2") (pinfunction "2_2") (pintype "passive"))
      (node (ref "U5") (pin "7") (pinfunction "CANH_7") (pintype "output"))
      (node (ref "U7") (pin "6") (pinfunction "6_6") (pintype "passive"))
    )
    (net (code "38") (name "Net-(U5-CANL)") (class "Default")
      (node (ref "R13") (pin "1") (pinfunction "1_1") (pintype "passive"))
      (node (ref "R14") (pin "1") (pinfunction "1_1") (pintype "passive"))
      (node (ref "U5") (pin "6") (pinfunction "CANL_6") (pintype "output"))
      (node (ref "U7") (pin "4") (pinfunction "4_4") (pintype "passive"))
    )
    (net (code "39") (name "Net-(U5-RXD)") (class "Default")
      (node (ref "R11") (pin "2") (pinfunction "2_2") (pintype "passive"))
      (node (ref "U5") (pin "4") (pinfunction "RXD_4") (pintype "input"))
    )
    (net (code "40") (name "Net-(U5-TXD)") (class "Default")
      (node (ref "R12") (pin "2") (pinfunction "2_2") (pintype "passive"))
      (node (ref "U5") (pin "1") (pinfunction "TXD_1") (pintype "input"))
    )
    (net (code "41") (name "Net-(U5-VREF)") (class "Default")
      (node (ref "C14") (pin "1") (pinfunction "1_1") (pintype "passive"))
      (node (ref "U5") (pin "5") (pinfunction "VREF_5") (pintype "input"))
    )
    (net (code "42") (name "unconnected-(J2-Pad3)") (class "Default")
      (node (ref "J2") (pin "3") (pinfunction "3_3") (pintype "bidirectional+no_connect"))
    )
    (net (code "43") (name "unconnected-(J4-ID-Pad4)") (class "Default")
      (node (ref "J4") (pin "4") (pinfunction "ID_4") (pintype "power_in+no_connect"))
    )
    (net (code "44") (name "unconnected-(U1-PA0_WKUP-Pad10)") (class "Default")
      (node (ref "U1") (pin "10") (pinfunction "PA0_WKUP_10") (pintype "bidirectional"))
    )
    (net (code "45") (name "unconnected-(U1-PA1-Pad11)") (class "Default")
      (node (ref "U1") (pin "11") (pinfunction "PA1_11") (pintype "bidirectional"))
    )
    (net (code "46") (name "unconnected-(U1-PA2-Pad12)") (class "Default")
      (node (ref "U1") (pin "12") (pinfunction "PA2_12") (pintype "bidirectional"))
    )
    (net (code "47") (name "unconnected-(U1-PA3-Pad13)") (class "Default")
      (node (ref "U1") (pin "13") (pinfunction "PA3_13") (pintype "bidirectional"))
    )
    (net (code "48") (name "unconnected-(U1-PA5-Pad15)") (class "Default")
      (node (ref "U1") (pin "15") (pinfunction "PA5_15") (pintype "bidirectional"))
    )
    (net (code "49") (name "unconnected-(U1-PA6-Pad16)") (class "Default")
      (node (ref "U1") (pin "16") (pinfunction "PA6_16") (pintype "bidirectional"))
    )
    (net (code "50") (name "unconnected-(U1-PA7-Pad17)") (class "Default")
      (node (ref "U1") (pin "17") (pinfunction "PA7_17") (pintype "bidirectional"))
    )
    (net (code "51") (name "unconnected-(U1-PA15-Pad38)") (class "Default")
      (node (ref "U1") (pin "38") (pinfunction "PA15_38") (pintype "bidirectional"))
    )
    (net (code "52") (name "unconnected-(U1-PB0-Pad18)") (class "Default")
      (node (ref "U1") (pin "18") (pinfunction "PB0_18") (pintype "bidirectional"))
    )
    (net (code "53") (name "unconnected-(U1-PB1-Pad19)") (class "Default")
      (node (ref "U1") (pin "19") (pinfunction "PB1_19") (pintype "bidirectional"))
    )
    (net (code "54") (name "unconnected-(U1-PB2-Pad20)") (class "Default")
      (node (ref "U1") (pin "20") (pinfunction "PB2_20") (pintype "bidirectional"))
    )
    (net (code "55") (name "unconnected-(U1-PB3-Pad39)") (class "Default")
      (node (ref "U1") (pin "39") (pinfunction "PB3_39") (pintype "bidirectional"))
    )
    (net (code "56") (name "unconnected-(U1-PB4-Pad40)") (class "Default")
      (node (ref "U1") (pin "40") (pinfunction "PB4_40") (pintype "bidirectional"))
    )
    (net (code "57") (name "unconnected-(U1-PB5-Pad41)") (class "Default")
      (node (ref "U1") (pin "41") (pinfunction "PB5_41") (pintype "bidirectional"))
    )
    (net (code "58") (name "unconnected-(U1-PB6-Pad42)") (class "Default")
      (node (ref "U1") (pin "42") (pinfunction "PB6_42") (pintype "bidirectional"))
    )
    (net (code "59") (name "unconnected-(U1-PB10-Pad21)") (class "Default")
      (node (ref "U1") (pin "21") (pinfunction "PB10_21") (pintype "bidirectional"))
    )
    (net (code "60") (name "unconnected-(U1-PB11-Pad22)") (class "Default")
      (node (ref "U1") (pin "22") (pinfunction "PB11_22") (pintype "bidirectional"))
    )
    (net (code "61") (name "unconnected-(U1-PB12-Pad25)") (class "Default")
      (node (ref "U1") (pin "25") (pinfunction "PB12_25") (pintype "bidirectional"))
    )
    (net (code "62") (name "unconnected-(U1-PB13-Pad26)") (class "Default")
      (node (ref "U1") (pin "26") (pinfunction "PB13_26") (pintype "bidirectional"))
    )
    (net (code "63") (name "unconnected-(U1-PB15-Pad28)") (class "Default")
      (node (ref "U1") (pin "28") (pinfunction "PB15_28") (pintype "bidirectional"))
    )
    (net (code "64") (name "unconnected-(U1-PC13-TAMPER-RTC-Pad2)") (class "Default")
      (node (ref "U1") (pin "2") (pinfunction "PC13-TAMPER-RTC_2") (pintype "bidirectional"))
    )
    (net (code "65") (name "unconnected-(U1-PC14-OSC32_IN-Pad3)") (class "Default")
      (node (ref "U1") (pin "3") (pinfunction "PC14-OSC32_IN_3") (pintype "bidirectional"))
    )
    (net (code "66") (name "unconnected-(U1-PC15-OSC32_OUT-Pad4)") (class "Default")
      (node (ref "U1") (pin "4") (pinfunction "PC15-OSC32_OUT_4") (pintype "bidirectional"))
    )
    (net (code "67") (name "unconnected-(U1-VBAT-Pad1)") (class "Default")
      (node (ref "U1") (pin "1") (pinfunction "VBAT_1") (pintype "bidirectional"))
    )
    (net (code "68") (name "unconnected-(U3-Pad1)") (class "Default")
      (node (ref "U3") (pin "1") (pinfunction "1_1") (pintype "passive+no_connect"))
    )
    (net (code "69") (name "unconnected-(U3-Pad3)") (class "Default")
      (node (ref "U3") (pin "3") (pinfunction "3_3") (pintype "passive+no_connect"))
    )
    (net (code "70") (name "unconnected-(U7-Pad1)") (class "Default")
      (node (ref "U7") (pin "1") (pinfunction "1_1") (pintype "passive"))
    )
    (net (code "71") (name "unconnected-(U7-Pad3)") (class "Default")
      (node (ref "U7") (pin "3") (pinfunction "3_3") (pintype "passive"))
    )
  )
)
